# 17_CAN_BUS.net
KiCad netlist of a schematic drawn in Altium Designer
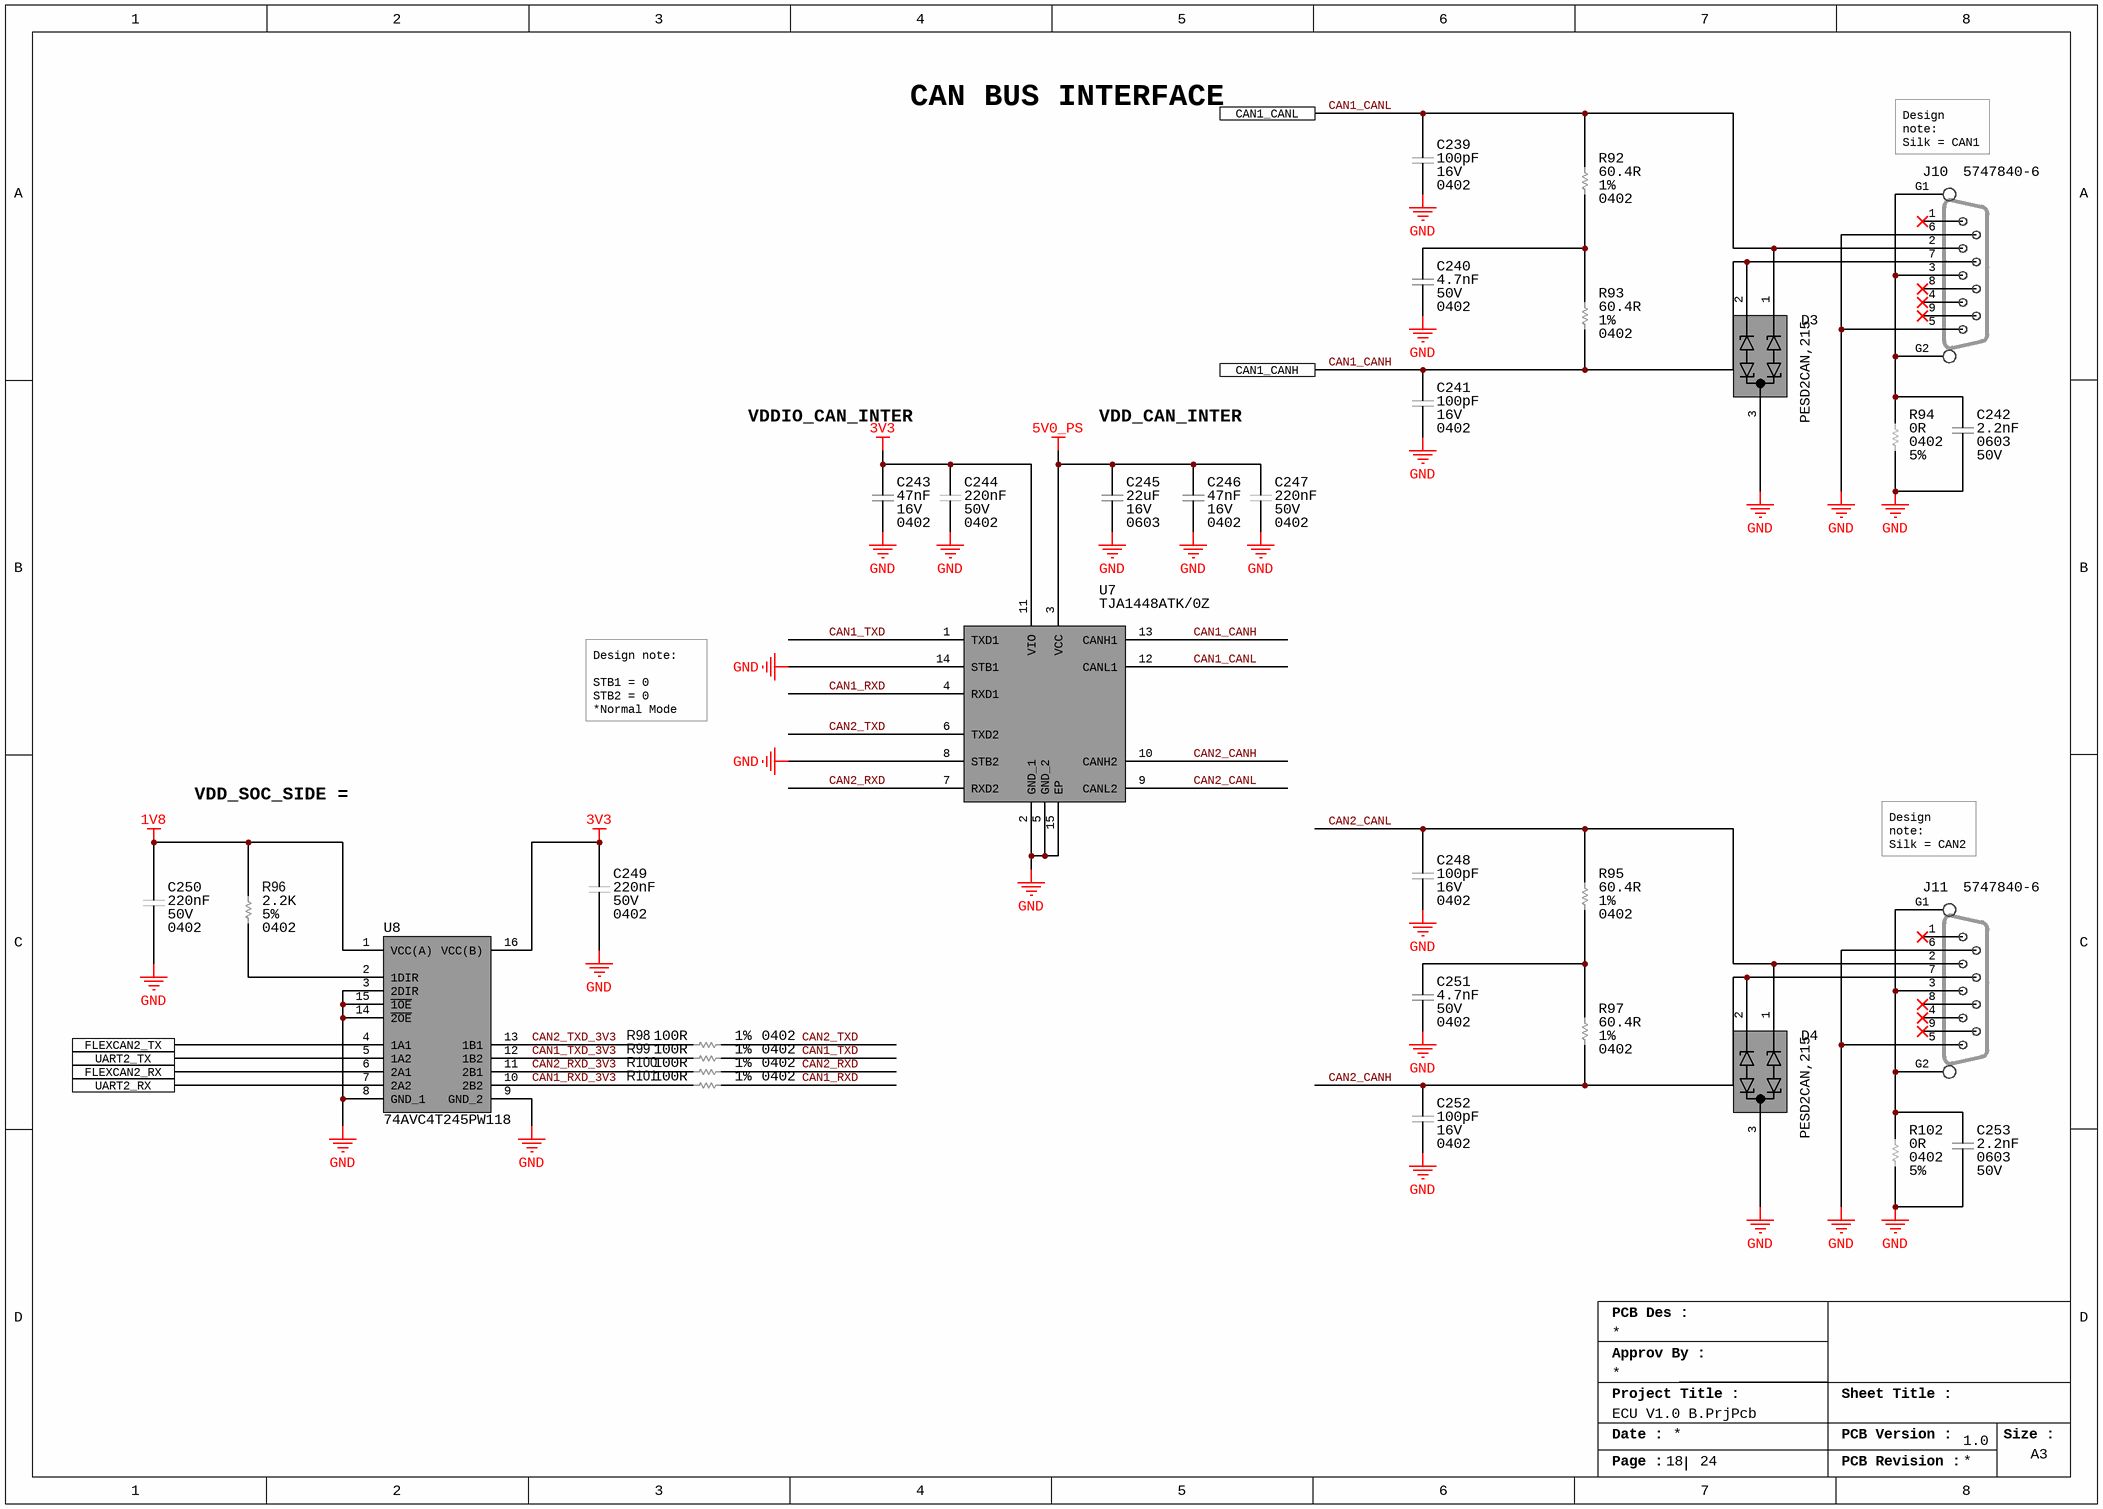
[diagram p0: 17_CAN_BUS.SchDoc]

(export (version "E")
  (design (tool "Eeschema 10.0.6"))
  (components
    (comp (ref "C239")
      (value "CC0402JRNPO7BN101")
      (footprint "CAP_0402_CAPC1005X05N")
      (description "0402 100 pF 16 V ±5 % Tolerance NP0 SMT Multilayer Ceramic Capacitor")
      (fields
        (field (name "MANUFACTURER") "Yageo")
        (field (name "TOLERANCE") "5%")
        (field (name "VOLTAGE RATING (DC)") "16V")
        (field (name "CAPACITANCE") "100pF")
        (field (name "CASE/PACKAGE") "0402")
      )
      (libsource (lib "Electronic Devices_LIB") (part "CAP_100PF_16V_NP0_0402"))
    )
    (comp (ref "C240")
      (value "GRM155R61H472KA01D")
      (footprint "CAP_0402_CAPC1005X05N")
      (description "Multilayer Ceramic Capacitor, 100 uF, 16 V, ± 20%, X5R, 1210 [3225 Metric]")
      (fields
        (field (name "MANUFACTURER") "Murata")
        (field (name "TOLERANCE") "10%")
        (field (name "VOLTAGE RATING") "50V")
        (field (name "CAPACITANCE") "4.7nF")
        (field (name "CASE/PACKAGE") "0402")
      )
      (libsource (lib "Electronic Devices_LIB") (part "CAP_4700PF_50V_X5R_0402"))
    )
    (comp (ref "C241")
      (value "CC0402JRNPO7BN101")
      (footprint "CAP_0402_CAPC1005X05N")
      (description "0402 100 pF 16 V ±5 % Tolerance NP0 SMT Multilayer Ceramic Capacitor")
      (fields
        (field (name "MANUFACTURER") "Yageo")
        (field (name "TOLERANCE") "5%")
        (field (name "VOLTAGE RATING (DC)") "16V")
        (field (name "CAPACITANCE") "100pF")
        (field (name "CASE/PACKAGE") "0402")
      )
      (libsource (lib "Electronic Devices_LIB") (part "CAP_100PF_16V_NP0_0402"))
    )
    (comp (ref "C242")
      (value "GRM1885C1H222JA01D")
      (footprint "CAP_0603_CAPC1608X08N")
      (description "Multilayer Ceramic Capacitor, 2200 pF, 50 V, ï¿½ 5%, C0G (NP0), 0603 [1608 Metric]")
      (fields
        (field (name "MANUFACTURER") "Murata")
        (field (name "TOLERANCE") "5%")
        (field (name "CASE/PACKAGE") "0603")
        (field (name "VOLTAGE RATING") "50V")
        (field (name "CAPACITANCE") "2.2nF")
      )
      (libsource (lib "Electronic Devices_LIB") (part "CAP_2.2nF_50V_NP0_0402"))
    )
    (comp (ref "C243")
      (value "GCM155R71C473KA37D")
      (footprint "CAP_0402_CAPC1005X05N")
      (description "Multilayer Ceramic Capacitor, 0.047 uF, 16 V, ± 10%, X7R, 0402 [1005 Metric]")
      (fields
        (field (name "MANUFACTURER") "Murata")
        (field (name "TOLERANCE") "10%")
        (field (name "CAPACITANCE") "47nF")
        (field (name "VOLTAGE RATING") "16V")
        (field (name "CASE/PACKAGE") "0402")
      )
      (libsource (lib "Electronic Devices_LIB") (part "CAP_47nF_16V_X7R_0402"))
    )
    (comp (ref "C244")
      (value "GRM155R61H224KE01W")
      (footprint "CAP_0402_CAPC1005X05N")
      (description "Multilayer Ceramic Capacitor, 0.22 uF, 50 VDC, ± 10%, X5R, 0402 [1005 Metric]")
      (fields
        (field (name "MANUFACTURER") "Murata")
        (field (name "CASE/PACKAGE") "0402")
        (field (name "VOLTAGE RATING (DC)") "50V")
        (field (name "CAPACITANCE") "220nF")
      )
      (libsource (lib "Electronic Devices_LIB") (part "CAP_0.22UF_50V_X5R_0402"))
    )
    (comp (ref "C245")
      (value "CL10A226MO7JZNC")
      (footprint "CAP_0603_CAPC1608X08N")
      (description "Cap Ceramic 22uF 16V X5R 20% Pad SMD 0603 85C T/R")
      (fields
        (field (name "MANUFACTURER") "Samsung")
        (field (name "TOLERANCE") "20%")
        (field (name "CAPACITANCE") "22uF")
        (field (name "VOLTAGE RATING") "16V")
        (field (name "CASE/PACKAGE") "0603")
      )
      (libsource (lib "Electronic Devices_LIB") (part "CAP_22UF_16V_X5R_0603"))
    )
    (comp (ref "C246")
      (value "GCM155R71C473KA37D")
      (footprint "CAP_0402_CAPC1005X05N")
      (description "Multilayer Ceramic Capacitor, 0.047 uF, 16 V, ± 10%, X7R, 0402 [1005 Metric]")
      (fields
        (field (name "MANUFACTURER") "Murata")
        (field (name "TOLERANCE") "10%")
        (field (name "CAPACITANCE") "47nF")
        (field (name "VOLTAGE RATING") "16V")
        (field (name "CASE/PACKAGE") "0402")
      )
      (libsource (lib "Electronic Devices_LIB") (part "CAP_47nF_16V_X7R_0402"))
    )
    (comp (ref "C247")
      (value "GRM155R61H224KE01W")
      (footprint "CAP_0402_CAPC1005X05N")
      (description "Multilayer Ceramic Capacitor, 0.22 uF, 50 VDC, ± 10%, X5R, 0402 [1005 Metric]")
      (fields
        (field (name "MANUFACTURER") "Murata")
        (field (name "CASE/PACKAGE") "0402")
        (field (name "VOLTAGE RATING (DC)") "50V")
        (field (name "CAPACITANCE") "220nF")
      )
      (libsource (lib "Electronic Devices_LIB") (part "CAP_0.22UF_50V_X5R_0402"))
    )
    (comp (ref "C248")
      (value "CC0402JRNPO7BN101")
      (footprint "CAP_0402_CAPC1005X05N")
      (description "0402 100 pF 16 V ±5 % Tolerance NP0 SMT Multilayer Ceramic Capacitor")
      (fields
        (field (name "MANUFACTURER") "Yageo")
        (field (name "TOLERANCE") "5%")
        (field (name "VOLTAGE RATING (DC)") "16V")
        (field (name "CAPACITANCE") "100pF")
        (field (name "CASE/PACKAGE") "0402")
      )
      (libsource (lib "Electronic Devices_LIB") (part "CAP_100PF_16V_NP0_0402"))
    )
    (comp (ref "C249")
      (value "GRM155R61H224KE01W")
      (footprint "CAP_0402_CAPC1005X05N")
      (description "Multilayer Ceramic Capacitor, 0.22 uF, 50 VDC, ± 10%, X5R, 0402 [1005 Metric]")
      (fields
        (field (name "MANUFACTURER") "Murata")
        (field (name "CASE/PACKAGE") "0402")
        (field (name "VOLTAGE RATING (DC)") "50V")
        (field (name "CAPACITANCE") "220nF")
      )
      (libsource (lib "Electronic Devices_LIB") (part "CAP_0.22UF_50V_X5R_0402"))
    )
    (comp (ref "C250")
      (value "GRM155R61H224KE01W")
      (footprint "CAP_0402_CAPC1005X05N")
      (description "Multilayer Ceramic Capacitor, 0.22 uF, 50 VDC, ± 10%, X5R, 0402 [1005 Metric]")
      (fields
        (field (name "MANUFACTURER") "Murata")
        (field (name "CASE/PACKAGE") "0402")
        (field (name "VOLTAGE RATING (DC)") "50V")
        (field (name "CAPACITANCE") "220nF")
      )
      (libsource (lib "Electronic Devices_LIB") (part "CAP_0.22UF_50V_X5R_0402"))
    )
    (comp (ref "C251")
      (value "GRM155R61H472KA01D")
      (footprint "CAP_0402_CAPC1005X05N")
      (description "Multilayer Ceramic Capacitor, 100 uF, 16 V, ± 20%, X5R, 1210 [3225 Metric]")
      (fields
        (field (name "MANUFACTURER") "Murata")
        (field (name "TOLERANCE") "10%")
        (field (name "VOLTAGE RATING") "50V")
        (field (name "CAPACITANCE") "4.7nF")
        (field (name "CASE/PACKAGE") "0402")
      )
      (libsource (lib "Electronic Devices_LIB") (part "CAP_4700PF_50V_X5R_0402"))
    )
    (comp (ref "C252")
      (value "CC0402JRNPO7BN101")
      (footprint "CAP_0402_CAPC1005X05N")
      (description "0402 100 pF 16 V ±5 % Tolerance NP0 SMT Multilayer Ceramic Capacitor")
      (fields
        (field (name "MANUFACTURER") "Yageo")
        (field (name "TOLERANCE") "5%")
        (field (name "VOLTAGE RATING (DC)") "16V")
        (field (name "CAPACITANCE") "100pF")
        (field (name "CASE/PACKAGE") "0402")
      )
      (libsource (lib "Electronic Devices_LIB") (part "CAP_100PF_16V_NP0_0402"))
    )
    (comp (ref "C253")
      (value "GRM1885C1H222JA01D")
      (footprint "CAP_0603_CAPC1608X08N")
      (description "Multilayer Ceramic Capacitor, 2200 pF, 50 V, ï¿½ 5%, C0G (NP0), 0603 [1608 Metric]")
      (fields
        (field (name "MANUFACTURER") "Murata")
        (field (name "TOLERANCE") "5%")
        (field (name "CASE/PACKAGE") "0603")
        (field (name "VOLTAGE RATING") "50V")
        (field (name "CAPACITANCE") "2.2nF")
      )
      (libsource (lib "Electronic Devices_LIB") (part "CAP_2.2nF_50V_NP0_0402"))
    )
    (comp (ref "D3")
      (value "PESD2CAN,215")
      (footprint "DIO_PESD2CAN,215")
      (description "5A 230W 41V 26.2V Bidirectional 24V SOT-23 ESD and Surge Protection (TVS/ESD) ROHS")
      (fields (field (name "MANUFACTURER") "Nexperia"))
      (libsource (lib "Electronic Devices_LIB") (part "DIO_TVS_41V_5A_PESD2CAN,215"))
    )
    (comp (ref "D4")
      (value "PESD2CAN,215")
      (footprint "DIO_PESD2CAN,215")
      (description "5A 230W 41V 26.2V Bidirectional 24V SOT-23 ESD and Surge Protection (TVS/ESD) ROHS")
      (fields (field (name "MANUFACTURER") "Nexperia"))
      (libsource (lib "Electronic Devices_LIB") (part "DIO_TVS_41V_5A_PESD2CAN,215"))
    )
    (comp (ref "J10")
      (value "5747840-6")
      (footprint "TE_5747840-6")
      (description "D Subminiature Connector, 9 Contact(s), Male, 0.108 inch Pitch, Solder Terminal, #4-40, Plug")
      (fields (field (name "MANUFACTURER") "TE Connectivity"))
      (libsource (lib "Electronic Devices_LIB") (part "CONN_DB9_TEConnectivity_5747840-6"))
    )
    (comp (ref "J11")
      (value "5747840-6")
      (footprint "TE_5747840-6")
      (description "D Subminiature Connector, 9 Contact(s), Male, 0.108 inch Pitch, Solder Terminal, #4-40, Plug")
      (fields (field (name "MANUFACTURER") "TE Connectivity"))
      (libsource (lib "Electronic Devices_LIB") (part "CONN_DB9_TEConnectivity_5747840-6"))
    )
    (comp (ref "R92")
      (value "RK73H1ETTP60R4F")
      (footprint "RES_0402_RESC1005X04N")
      (description "Res Thick Film 0402 60.4 Ohm 1% 0.1W(1/10W) ±100ppm/C Pad SMD Automotive T/R")
      (fields
        (field (name "MANUFACTURER") "KOA Speer")
        (field (name "TOLERANCE") "1%")
        (field (name "RESISTANCE") "60.4R")
        (field (name "CASE/PACKAGE") "0402")
      )
      (libsource (lib "Electronic Devices_LIB") (part "RES_60.4R_1%_100mW_0402"))
    )
    (comp (ref "R93")
      (value "RK73H1ETTP60R4F")
      (footprint "RES_0402_RESC1005X04N")
      (description "Res Thick Film 0402 60.4 Ohm 1% 0.1W(1/10W) ±100ppm/C Pad SMD Automotive T/R")
      (fields
        (field (name "MANUFACTURER") "KOA Speer")
        (field (name "TOLERANCE") "1%")
        (field (name "RESISTANCE") "60.4R")
        (field (name "CASE/PACKAGE") "0402")
      )
      (libsource (lib "Electronic Devices_LIB") (part "RES_60.4R_1%_100mW_0402"))
    )
    (comp (ref "R94")
      (value "ERJ-2GE0R00X")
      (footprint "RES_0402_RESC1005X04N")
      (description "SMD Chip Resistor, Jumper, 0 ohm, 100 mW, 0402 [1005 Metric], Thick Film, General Purpose")
      (fields
        (field (name "MANUFACTURER") "Panasonic")
        (field (name "CASE CODE (IMPERIAL)") "0402")
        (field (name "TOLERANCE") "5%")
        (field (name "RESISTANCE") "0R")
      )
      (libsource (lib "Electronic Devices_LIB") (part "RES_0R_5%_100mW_0402"))
    )
    (comp (ref "R95")
      (value "RK73H1ETTP60R4F")
      (footprint "RES_0402_RESC1005X04N")
      (description "Res Thick Film 0402 60.4 Ohm 1% 0.1W(1/10W) ±100ppm/C Pad SMD Automotive T/R")
      (fields
        (field (name "MANUFACTURER") "KOA Speer")
        (field (name "TOLERANCE") "1%")
        (field (name "RESISTANCE") "60.4R")
        (field (name "CASE/PACKAGE") "0402")
      )
      (libsource (lib "Electronic Devices_LIB") (part "RES_60.4R_1%_100mW_0402"))
    )
    (comp (ref "R96")
      (value "RC0402JR-072K2L")
      (footprint "RES_0402_RESC1005X04N")
      (description "SMD Chip Resistor, 2.2 kOhm, ± 5%, 63 mW, 0402 [1005 Metric], Thick Film, General Purpose")
      (fields
        (field (name "MANUFACTURER") "Yageo")
        (field (name "TOLERANCE") "5%")
        (field (name "RESISTANCE") "2.2K")
        (field (name "CASE/PACKAGE") "0402")
      )
      (libsource (lib "Electronic Devices_LIB") (part "RES_2.2K_5%_63mW_0402"))
    )
    (comp (ref "R97")
      (value "RK73H1ETTP60R4F")
      (footprint "RES_0402_RESC1005X04N")
      (description "Res Thick Film 0402 60.4 Ohm 1% 0.1W(1/10W) ±100ppm/C Pad SMD Automotive T/R")
      (fields
        (field (name "MANUFACTURER") "KOA Speer")
        (field (name "TOLERANCE") "1%")
        (field (name "RESISTANCE") "60.4R")
        (field (name "CASE/PACKAGE") "0402")
      )
      (libsource (lib "Electronic Devices_LIB") (part "RES_60.4R_1%_100mW_0402"))
    )
    (comp (ref "R98")
      (value "ERJ-2RKF1000X")
      (footprint "RES_0402_RESC1005X04N")
      (description "Resistor Thick Film 0402 100 Ohm 1% 1/10W 100ppm/C Molded SMD Punched Carrier T/R")
      (fields
        (field (name "MANUFACTURER") "Panasonic")
        (field (name "TOLERANCE") "1%")
        (field (name "RESISTANCE") "100R")
        (field (name "CASE/PACKAGE") "0402")
      )
      (libsource (lib "Electronic Devices_LIB") (part "RES_100R_1%_100mW_0402"))
    )
    (comp (ref "R99")
      (value "ERJ-2RKF1000X")
      (footprint "RES_0402_RESC1005X04N")
      (description "Resistor Thick Film 0402 100 Ohm 1% 1/10W 100ppm/C Molded SMD Punched Carrier T/R")
      (fields
        (field (name "MANUFACTURER") "Panasonic")
        (field (name "TOLERANCE") "1%")
        (field (name "RESISTANCE") "100R")
        (field (name "CASE/PACKAGE") "0402")
      )
      (libsource (lib "Electronic Devices_LIB") (part "RES_100R_1%_100mW_0402"))
    )
    (comp (ref "R100")
      (value "ERJ-2RKF1000X")
      (footprint "RES_0402_RESC1005X04N")
      (description "Resistor Thick Film 0402 100 Ohm 1% 1/10W 100ppm/C Molded SMD Punched Carrier T/R")
      (fields
        (field (name "MANUFACTURER") "Panasonic")
        (field (name "TOLERANCE") "1%")
        (field (name "RESISTANCE") "100R")
        (field (name "CASE/PACKAGE") "0402")
      )
      (libsource (lib "Electronic Devices_LIB") (part "RES_100R_1%_100mW_0402"))
    )
    (comp (ref "R101")
      (value "ERJ-2RKF1000X")
      (footprint "RES_0402_RESC1005X04N")
      (description "Resistor Thick Film 0402 100 Ohm 1% 1/10W 100ppm/C Molded SMD Punched Carrier T/R")
      (fields
        (field (name "MANUFACTURER") "Panasonic")
        (field (name "TOLERANCE") "1%")
        (field (name "RESISTANCE") "100R")
        (field (name "CASE/PACKAGE") "0402")
      )
      (libsource (lib "Electronic Devices_LIB") (part "RES_100R_1%_100mW_0402"))
    )
    (comp (ref "R102")
      (value "ERJ-2GE0R00X")
      (footprint "RES_0402_RESC1005X04N")
      (description "SMD Chip Resistor, Jumper, 0 ohm, 100 mW, 0402 [1005 Metric], Thick Film, General Purpose")
      (fields
        (field (name "MANUFACTURER") "Panasonic")
        (field (name "CASE CODE (IMPERIAL)") "0402")
        (field (name "TOLERANCE") "5%")
        (field (name "RESISTANCE") "0R")
      )
      (libsource (lib "Electronic Devices_LIB") (part "RES_0R_5%_100mW_0402"))
    )
    (comp (ref "U7")
      (value "TJA1448ATK/0Z")
      (footprint "SON65P300X450X100-15N")
      (description "Can Transceiver with Standby Mode Dual High-Speed 5Mbps 4.5V to 5.5V 14-Pin HVSON")
      (fields (field (name "MANUFACTURER") "NXP Semiconductors"))
      (libsource (lib "Electronic Devices_LIB") (part "IC_TRANSCEIVER_CAN_TJA1448ATK/0Z"))
    )
    (comp (ref "U8")
      (value "74AVC4T245PW118")
      (footprint "SOP65P640X110-16N")
      (description "74Avc4T245Pw/Sot403/Tssop16 Rohs Compliant: Yes ¦Nexperia 74AVC4T245PW 118")
      (fields (field (name "MANUFACTURER") "Nexperia"))
      (libsource (lib "Electronic Devices_LIB") (part "IC_TRANSLATION_TXRX_74AVC4T245PW118"))
    )
  )
  (nets
    (net (code "1") (name "/CAN1_CANH") (class "Default")
      (node (ref "C241") (pin "2") (pinfunction "2_2") (pintype "passive"))
      (node (ref "D3") (pin "2") (pinfunction "C2_2") (pintype "passive"))
      (node (ref "J10") (pin "7") (pinfunction "7_7") (pintype "passive"))
      (node (ref "R93") (pin "1") (pinfunction "1_1") (pintype "passive"))
      (node (ref "U7") (pin "13") (pinfunction "CANH1_13") (pintype "passive"))
    )
    (net (code "2") (name "/CAN1_CANL") (class "Default")
      (node (ref "C239") (pin "2") (pinfunction "2_2") (pintype "passive"))
      (node (ref "D3") (pin "1") (pinfunction "C1_1") (pintype "passive"))
      (node (ref "J10") (pin "2") (pinfunction "2_2") (pintype "passive"))
      (node (ref "R92") (pin "2") (pinfunction "2_2") (pintype "passive"))
      (node (ref "U7") (pin "12") (pinfunction "CANL1_12") (pintype "passive"))
    )
    (net (code "3") (name "/CAN1_RXD") (class "Default")
      (node (ref "R101") (pin "2") (pinfunction "2_2") (pintype "passive"))
      (node (ref "U7") (pin "4") (pinfunction "RXD1_4") (pintype "passive"))
    )
    (net (code "4") (name "/CAN1_RXD_3V3") (class "Default")
      (node (ref "R101") (pin "1") (pinfunction "1_1") (pintype "passive"))
      (node (ref "U8") (pin "10") (pinfunction "2B2_10") (pintype "passive"))
    )
    (net (code "5") (name "/CAN1_TXD") (class "Default")
      (node (ref "R99") (pin "2") (pinfunction "2_2") (pintype "passive"))
      (node (ref "U7") (pin "1") (pinfunction "TXD1_1") (pintype "passive"))
    )
    (net (code "6") (name "/CAN1_TXD_3V3") (class "Default")
      (node (ref "R99") (pin "1") (pinfunction "1_1") (pintype "passive"))
      (node (ref "U8") (pin "12") (pinfunction "1B2_12") (pintype "passive"))
    )
    (net (code "7") (name "/CAN2_CANH") (class "Default")
      (node (ref "C252") (pin "2") (pinfunction "2_2") (pintype "passive"))
      (node (ref "D4") (pin "2") (pinfunction "C2_2") (pintype "passive"))
      (node (ref "J11") (pin "7") (pinfunction "7_7") (pintype "passive"))
      (node (ref "R97") (pin "1") (pinfunction "1_1") (pintype "passive"))
      (node (ref "U7") (pin "10") (pinfunction "CANH2_10") (pintype "passive"))
    )
    (net (code "8") (name "/CAN2_CANL") (class "Default")
      (node (ref "C248") (pin "2") (pinfunction "2_2") (pintype "passive"))
      (node (ref "D4") (pin "1") (pinfunction "C1_1") (pintype "passive"))
      (node (ref "J11") (pin "2") (pinfunction "2_2") (pintype "passive"))
      (node (ref "R95") (pin "2") (pinfunction "2_2") (pintype "passive"))
      (node (ref "U7") (pin "9") (pinfunction "CANL2_9") (pintype "passive"))
    )
    (net (code "9") (name "/CAN2_RXD") (class "Default")
      (node (ref "R100") (pin "2") (pinfunction "2_2") (pintype "passive"))
      (node (ref "U7") (pin "7") (pinfunction "RXD2_7") (pintype "passive"))
    )
    (net (code "10") (name "/CAN2_RXD_3V3") (class "Default")
      (node (ref "R100") (pin "1") (pinfunction "1_1") (pintype "passive"))
      (node (ref "U8") (pin "11") (pinfunction "2B1_11") (pintype "passive"))
    )
    (net (code "11") (name "/CAN2_TXD") (class "Default")
      (node (ref "R98") (pin "2") (pinfunction "2_2") (pintype "passive"))
      (node (ref "U7") (pin "6") (pinfunction "TXD2_6") (pintype "passive"))
    )
    (net (code "12") (name "/CAN2_TXD_3V3") (class "Default")
      (node (ref "R98") (pin "1") (pinfunction "1_1") (pintype "passive"))
      (node (ref "U8") (pin "13") (pinfunction "1B1_13") (pintype "passive"))
    )
    (net (code "13") (name "/FLEXCAN2_RX") (class "Default")
      (node (ref "U8") (pin "6") (pinfunction "2A1_6") (pintype "passive"))
    )
    (net (code "14") (name "/FLEXCAN2_TX") (class "Default")
      (node (ref "U8") (pin "4") (pinfunction "1A1_4") (pintype "passive"))
    )
    (net (code "15") (name "/UART2_RX") (class "Default")
      (node (ref "U8") (pin "7") (pinfunction "2A2_7") (pintype "passive"))
    )
    (net (code "16") (name "/UART2_TX") (class "Default")
      (node (ref "U8") (pin "5") (pinfunction "1A2_5") (pintype "passive"))
    )
    (net (code "17") (name "1V8") (class "Default")
      (node (ref "C250") (pin "2") (pinfunction "2_2") (pintype "passive"))
      (node (ref "R96") (pin "2") (pinfunction "2_2") (pintype "passive"))
      (node (ref "U8") (pin "1") (pinfunction "VCC(A)_1") (pintype "passive"))
    )
    (net (code "18") (name "3V3") (class "Default")
      (node (ref "C243") (pin "2") (pinfunction "2_2") (pintype "passive"))
      (node (ref "C244") (pin "1") (pinfunction "1_1") (pintype "passive"))
      (node (ref "C249") (pin "2") (pinfunction "2_2") (pintype "passive"))
      (node (ref "U7") (pin "11") (pinfunction "VIO_11") (pintype "passive"))
      (node (ref "U8") (pin "16") (pinfunction "VCC(B)_16") (pintype "passive"))
    )
    (net (code "19") (name "5V0_PS") (class "Default")
      (node (ref "C245") (pin "2") (pinfunction "2_2") (pintype "passive"))
      (node (ref "C246") (pin "2") (pinfunction "2_2") (pintype "passive"))
      (node (ref "C247") (pin "1") (pinfunction "1_1") (pintype "passive"))
      (node (ref "U7") (pin "3") (pinfunction "VCC_3") (pintype "passive"))
    )
    (net (code "20") (name "GND") (class "Default")
      (node (ref "C239") (pin "1") (pinfunction "1_1") (pintype "passive"))
      (node (ref "C240") (pin "1") (pinfunction "1_1") (pintype "passive"))
      (node (ref "C241") (pin "1") (pinfunction "1_1") (pintype "passive"))
      (node (ref "C242") (pin "1") (pinfunction "1_1") (pintype "passive"))
      (node (ref "C243") (pin "1") (pinfunction "1_1") (pintype "passive"))
      (node (ref "C244") (pin "2") (pinfunction "2_2") (pintype "passive"))
      (node (ref "C245") (pin "1") (pinfunction "1_1") (pintype "passive"))
      (node (ref "C246") (pin "1") (pinfunction "1_1") (pintype "passive"))
      (node (ref "C247") (pin "2") (pinfunction "2_2") (pintype "passive"))
      (node (ref "C248") (pin "1") (pinfunction "1_1") (pintype "passive"))
      (node (ref "C249") (pin "1") (pinfunction "1_1") (pintype "passive"))
      (node (ref "C250") (pin "1") (pinfunction "1_1") (pintype "passive"))
      (node (ref "C251") (pin "1") (pinfunction "1_1") (pintype "passive"))
      (node (ref "C252") (pin "1") (pinfunction "1_1") (pintype "passive"))
      (node (ref "C253") (pin "1") (pinfunction "1_1") (pintype "passive"))
      (node (ref "D3") (pin "3") (pinfunction "CC_3") (pintype "passive"))
      (node (ref "D4") (pin "3") (pinfunction "CC_3") (pintype "passive"))
      (node (ref "J10") (pin "5") (pinfunction "5_5") (pintype "passive"))
      (node (ref "J10") (pin "6") (pinfunction "6_6") (pintype "passive"))
      (node (ref "J11") (pin "5") (pinfunction "5_5") (pintype "passive"))
      (node (ref "J11") (pin "6") (pinfunction "6_6") (pintype "passive"))
      (node (ref "R102") (pin "1") (pinfunction "1_1") (pintype "passive"))
      (node (ref "R94") (pin "1") (pinfunction "1_1") (pintype "passive"))
      (node (ref "U7") (pin "14") (pinfunction "STB1_14") (pintype "passive"))
      (node (ref "U7") (pin "15") (pinfunction "EP_15") (pintype "passive"))
      (node (ref "U7") (pin "2") (pinfunction "GND_1_2") (pintype "passive"))
      (node (ref "U7") (pin "5") (pinfunction "GND_2_5") (pintype "passive"))
      (node (ref "U7") (pin "8") (pinfunction "STB2_8") (pintype "passive"))
      (node (ref "U8") (pin "14") (pinfunction "~{2OE}_14") (pintype "passive"))
      (node (ref "U8") (pin "15") (pinfunction "~{1OE}_15") (pintype "passive"))
      (node (ref "U8") (pin "3") (pinfunction "2DIR_3") (pintype "passive"))
      (node (ref "U8") (pin "8") (pinfunction "GND_1_8") (pintype "passive"))
      (node (ref "U8") (pin "9") (pinfunction "GND_2_9") (pintype "passive"))
    )
    (net (code "21") (name "Net-(C240-Pad2)") (class "Default")
      (node (ref "C240") (pin "2") (pinfunction "2_2") (pintype "passive"))
      (node (ref "R92") (pin "1") (pinfunction "1_1") (pintype "passive"))
      (node (ref "R93") (pin "2") (pinfunction "2_2") (pintype "passive"))
    )
    (net (code "22") (name "Net-(C251-Pad2)") (class "Default")
      (node (ref "C251") (pin "2") (pinfunction "2_2") (pintype "passive"))
      (node (ref "R95") (pin "1") (pinfunction "1_1") (pintype "passive"))
      (node (ref "R97") (pin "2") (pinfunction "2_2") (pintype "passive"))
    )
    (net (code "23") (name "Net-(J10-G)") (class "Default")
      (node (ref "C242") (pin "2") (pinfunction "2_2") (pintype "passive"))
      (node (ref "J10") (pin "3") (pinfunction "3_3") (pintype "passive"))
      (node (ref "J10") (pin "G1") (pinfunction "G1_G1") (pintype "passive"))
      (node (ref "J10") (pin "G2") (pinfunction "G_G2") (pintype "passive"))
      (node (ref "R94") (pin "2") (pinfunction "2_2") (pintype "passive"))
    )
    (net (code "24") (name "Net-(J11-G)") (class "Default")
      (node (ref "C253") (pin "2") (pinfunction "2_2") (pintype "passive"))
      (node (ref "J11") (pin "3") (pinfunction "3_3") (pintype "passive"))
      (node (ref "J11") (pin "G1") (pinfunction "G1_G1") (pintype "passive"))
      (node (ref "J11") (pin "G2") (pinfunction "G_G2") (pintype "passive"))
      (node (ref "R102") (pin "2") (pinfunction "2_2") (pintype "passive"))
    )
    (net (code "25") (name "Net-(U8-1DIR)") (class "Default")
      (node (ref "R96") (pin "1") (pinfunction "1_1") (pintype "passive"))
      (node (ref "U8") (pin "2") (pinfunction "1DIR_2") (pintype "passive"))
    )
    (net (code "26") (name "unconnected-(J10-Pad1)") (class "Default")
      (node (ref "J10") (pin "1") (pinfunction "1_1") (pintype "passive+no_connect"))
    )
    (net (code "27") (name "unconnected-(J10-Pad4)") (class "Default")
      (node (ref "J10") (pin "4") (pinfunction "4_4") (pintype "passive+no_connect"))
    )
    (net (code "28") (name "unconnected-(J10-Pad8)") (class "Default")
      (node (ref "J10") (pin "8") (pinfunction "8_8") (pintype "passive+no_connect"))
    )
    (net (code "29") (name "unconnected-(J10-Pad9)") (class "Default")
      (node (ref "J10") (pin "9") (pinfunction "9_9") (pintype "passive+no_connect"))
    )
    (net (code "30") (name "unconnected-(J11-Pad1)") (class "Default")
      (node (ref "J11") (pin "1") (pinfunction "1_1") (pintype "passive+no_connect"))
    )
    (net (code "31") (name "unconnected-(J11-Pad4)") (class "Default")
      (node (ref "J11") (pin "4") (pinfunction "4_4") (pintype "passive+no_connect"))
    )
    (net (code "32") (name "unconnected-(J11-Pad8)") (class "Default")
      (node (ref "J11") (pin "8") (pinfunction "8_8") (pintype "passive+no_connect"))
    )
    (net (code "33") (name "unconnected-(J11-Pad9)") (class "Default")
      (node (ref "J11") (pin "9") (pinfunction "9_9") (pintype "passive+no_connect"))
    )
  )
)
